# Client_Esp32.net
KiCad netlist of a schematic drawn in Altium Designer
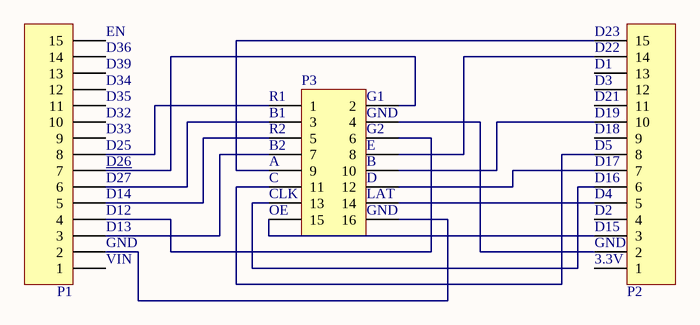
[diagram p0: Client_Esp32.SchDoc]

(export (version "E")
  (design (tool "Eeschema 10.0.6"))
  (components
    (comp (ref "P1")
      (value "Header 15")
      (footprint "HDR1X15")
      (description "Header, 15-Pin")
      (fields (field (name "PUBLISHER") "Altium Limited"))
      (libsource (lib "Miscellaneous Connectors") (part "Header 15"))
    )
    (comp (ref "P2")
      (value "Header 15")
      (footprint "HDR1X15")
      (description "Header, 15-Pin")
      (fields (field (name "PUBLISHER") "Altium Limited"))
      (libsource (lib "") (part "Header 15_1"))
    )
    (comp (ref "P3")
      (value "Header 8X2")
      (footprint "HDR2X8")
      (description "Header, 8-Pin, Dual row")
      (fields (field (name "PUBLISHER") "Altium Limited"))
      (libsource (lib "Miscellaneous Connectors") (part "Header 8X2"))
    )
  )
  (nets
    (net (code "1") (name "Net-(P1-Pad2)") (class "Default")
      (node (ref "P1") (pin "2") (pinfunction "2_2") (pintype "passive"))
      (node (ref "P3") (pin "16") (pinfunction "16_16") (pintype "passive"))
    )
    (net (code "2") (name "Net-(P1-Pad3)") (class "Default")
      (node (ref "P1") (pin "3") (pinfunction "3_3") (pintype "passive"))
      (node (ref "P3") (pin "7") (pinfunction "7_7") (pintype "passive"))
    )
    (net (code "3") (name "Net-(P1-Pad4)") (class "Default")
      (node (ref "P1") (pin "4") (pinfunction "4_4") (pintype "passive"))
      (node (ref "P3") (pin "6") (pinfunction "6_6") (pintype "passive"))
    )
    (net (code "4") (name "Net-(P1-Pad5)") (class "Default")
      (node (ref "P1") (pin "5") (pinfunction "5_5") (pintype "passive"))
      (node (ref "P3") (pin "5") (pinfunction "5_5") (pintype "passive"))
    )
    (net (code "5") (name "Net-(P1-Pad6)") (class "Default")
      (node (ref "P1") (pin "6") (pinfunction "6_6") (pintype "passive"))
      (node (ref "P3") (pin "3") (pinfunction "3_3") (pintype "passive"))
    )
    (net (code "6") (name "Net-(P1-Pad7)") (class "Default")
      (node (ref "P1") (pin "7") (pinfunction "7_7") (pintype "passive"))
      (node (ref "P3") (pin "2") (pinfunction "2_2") (pintype "passive"))
    )
    (net (code "7") (name "Net-(P1-Pad8)") (class "Default")
      (node (ref "P1") (pin "8") (pinfunction "8_8") (pintype "passive"))
      (node (ref "P3") (pin "1") (pinfunction "1_1") (pintype "passive"))
    )
    (net (code "8") (name "Net-(P2-Pad2)") (class "Default")
      (node (ref "P2") (pin "2") (pinfunction "2_2") (pintype "passive"))
      (node (ref "P3") (pin "4") (pinfunction "4_4") (pintype "passive"))
    )
    (net (code "9") (name "Net-(P2-Pad3)") (class "Default")
      (node (ref "P2") (pin "3") (pinfunction "3_3") (pintype "passive"))
      (node (ref "P3") (pin "15") (pinfunction "15_15") (pintype "passive"))
    )
    (net (code "10") (name "Net-(P2-Pad5)") (class "Default")
      (node (ref "P2") (pin "5") (pinfunction "5_5") (pintype "passive"))
      (node (ref "P3") (pin "14") (pinfunction "14_14") (pintype "passive"))
    )
    (net (code "11") (name "Net-(P2-Pad6)") (class "Default")
      (node (ref "P2") (pin "6") (pinfunction "6_6") (pintype "passive"))
      (node (ref "P3") (pin "13") (pinfunction "13_13") (pintype "passive"))
    )
    (net (code "12") (name "Net-(P2-Pad7)") (class "Default")
      (node (ref "P2") (pin "7") (pinfunction "7_7") (pintype "passive"))
      (node (ref "P3") (pin "12") (pinfunction "12_12") (pintype "passive"))
    )
    (net (code "13") (name "Net-(P2-Pad8)") (class "Default")
      (node (ref "P2") (pin "8") (pinfunction "8_8") (pintype "passive"))
      (node (ref "P3") (pin "11") (pinfunction "11_11") (pintype "passive"))
    )
    (net (code "14") (name "Net-(P2-Pad10)") (class "Default")
      (node (ref "P2") (pin "10") (pinfunction "10_10") (pintype "passive"))
      (node (ref "P3") (pin "10") (pinfunction "10_10") (pintype "passive"))
    )
    (net (code "15") (name "Net-(P2-Pad14)") (class "Default")
      (node (ref "P2") (pin "14") (pinfunction "14_14") (pintype "passive"))
      (node (ref "P3") (pin "8") (pinfunction "8_8") (pintype "passive"))
    )
    (net (code "16") (name "Net-(P2-Pad15)") (class "Default")
      (node (ref "P2") (pin "15") (pinfunction "15_15") (pintype "passive"))
      (node (ref "P3") (pin "9") (pinfunction "9_9") (pintype "passive"))
    )
    (net (code "17") (name "unconnected-(P1-Pad1)") (class "Default")
      (node (ref "P1") (pin "1") (pinfunction "1_1") (pintype "passive"))
    )
    (net (code "18") (name "unconnected-(P1-Pad9)") (class "Default")
      (node (ref "P1") (pin "9") (pinfunction "9_9") (pintype "passive"))
    )
    (net (code "19") (name "unconnected-(P1-Pad10)") (class "Default")
      (node (ref "P1") (pin "10") (pinfunction "10_10") (pintype "passive"))
    )
    (net (code "20") (name "unconnected-(P1-Pad11)") (class "Default")
      (node (ref "P1") (pin "11") (pinfunction "11_11") (pintype "passive"))
    )
    (net (code "21") (name "unconnected-(P1-Pad12)") (class "Default")
      (node (ref "P1") (pin "12") (pinfunction "12_12") (pintype "passive"))
    )
    (net (code "22") (name "unconnected-(P1-Pad13)") (class "Default")
      (node (ref "P1") (pin "13") (pinfunction "13_13") (pintype "passive"))
    )
    (net (code "23") (name "unconnected-(P1-Pad14)") (class "Default")
      (node (ref "P1") (pin "14") (pinfunction "14_14") (pintype "passive"))
    )
    (net (code "24") (name "unconnected-(P1-Pad15)") (class "Default")
      (node (ref "P1") (pin "15") (pinfunction "15_15") (pintype "passive"))
    )
    (net (code "25") (name "unconnected-(P2-Pad1)") (class "Default")
      (node (ref "P2") (pin "1") (pinfunction "1_1") (pintype "passive"))
    )
    (net (code "26") (name "unconnected-(P2-Pad4)") (class "Default")
      (node (ref "P2") (pin "4") (pinfunction "4_4") (pintype "passive"))
    )
    (net (code "27") (name "unconnected-(P2-Pad9)") (class "Default")
      (node (ref "P2") (pin "9") (pinfunction "9_9") (pintype "passive"))
    )
    (net (code "28") (name "unconnected-(P2-Pad11)") (class "Default")
      (node (ref "P2") (pin "11") (pinfunction "11_11") (pintype "passive"))
    )
    (net (code "29") (name "unconnected-(P2-Pad12)") (class "Default")
      (node (ref "P2") (pin "12") (pinfunction "12_12") (pintype "passive"))
    )
    (net (code "30") (name "unconnected-(P2-Pad13)") (class "Default")
      (node (ref "P2") (pin "13") (pinfunction "13_13") (pintype "passive"))
    )
  )
)
